# 8ball.net
KiCad netlist of a schematic drawn in EAGLE
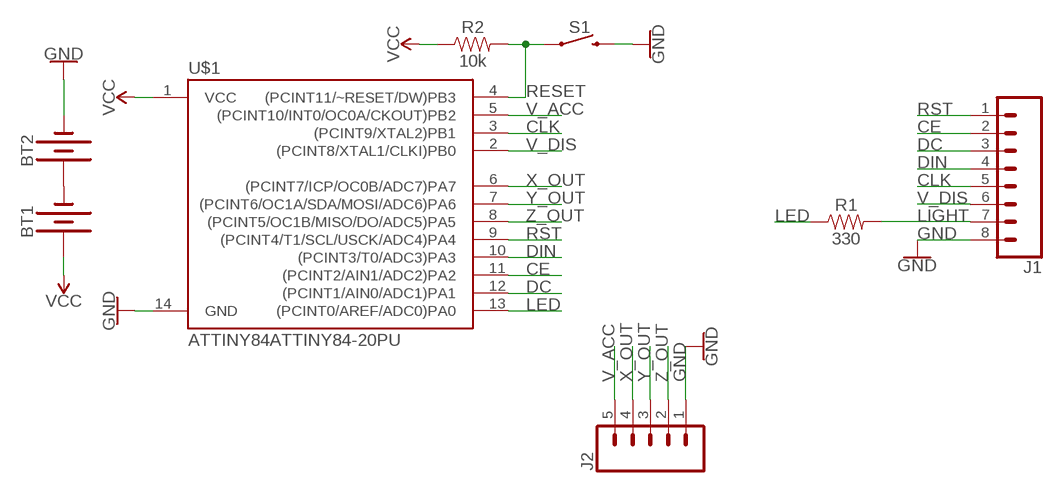
[diagram p0: schematic, sheet 1]

(export (version "E")
  (design (tool "Eeschema 10.0.6"))
  (components
    (comp (ref "BT1")
      (value "BATTERY-AAA")
      (footprint "eagle-import:BATTERY-AAA")
      (libsource (lib "eagle-import") (part "BATTERY-AAA"))
    )
    (comp (ref "BT2")
      (value "BATTERY-AAA")
      (footprint "eagle-import:BATTERY-AAA")
      (libsource (lib "eagle-import") (part "BATTERY-AAA"))
    )
    (comp (ref "J1")
      (value "CONN_08FEMALE_LOCK")
      (footprint "eagle-import:1X08_FEMALE_LOCK")
      (libsource (lib "eagle-import") (part "CONN_08FEMALE_LOCK"))
    )
    (comp (ref "J2")
      (value "CONN_05LOCK")
      (footprint "eagle-import:1X05_LOCK")
      (libsource (lib "eagle-import") (part "CONN_05LOCK"))
    )
    (comp (ref "R1")
      (value "330")
      (footprint "eagle-import:AXIAL-0.3")
      (libsource (lib "eagle-import") (part "330OHM-HORIZ-1/10W-5%"))
    )
    (comp (ref "R2")
      (value "10k")
      (footprint "eagle-import:AXIAL-0.3")
      (libsource (lib "eagle-import") (part "10KOHM-HORIZ-1/6W-5%"))
    )
    (comp (ref "S1")
      (value "MOMENTARY-SWITCH-SPST-PTH-6.0MM-KIT")
      (footprint "eagle-import:TACTILE_SWITCH_PTH_6.0MM_KIT")
      (libsource (lib "eagle-import") (part "MOMENTARY-SWITCH-SPST-PTH-6.0MM-KIT"))
    )
    (comp (ref "U$1")
      (value "ATTINY84ATTINY84-20PU")
      (footprint "eagle-import:DIP14")
      (libsource (lib "eagle-import") (part "ATTINY84ATTINY84-20PU"))
    )
  )
  (nets
    (net (code "1") (name "/CE") (class "Default")
      (node (ref "J1") (pin "2") (pinfunction "2_2") (pintype "passive"))
      (node (ref "U$1") (pin "11") (pinfunction "(PCINT2/AIN1/ADC2)PA2_11") (pintype "bidirectional"))
    )
    (net (code "2") (name "/CLK") (class "Default")
      (node (ref "J1") (pin "5") (pinfunction "5_5") (pintype "passive"))
      (node (ref "U$1") (pin "3") (pinfunction "(PCINT9/XTAL2)PB1_3") (pintype "bidirectional"))
    )
    (net (code "3") (name "/DC") (class "Default")
      (node (ref "J1") (pin "3") (pinfunction "3_3") (pintype "passive"))
      (node (ref "U$1") (pin "12") (pinfunction "(PCINT1/AIN0/ADC1)PA1_12") (pintype "bidirectional"))
    )
    (net (code "4") (name "/DIN") (class "Default")
      (node (ref "J1") (pin "4") (pinfunction "4_4") (pintype "passive"))
      (node (ref "U$1") (pin "10") (pinfunction "(PCINT3/T0/ADC3)PA3_10") (pintype "bidirectional"))
    )
    (net (code "5") (name "/LED") (class "Default")
      (node (ref "R1") (pin "P$1") (pinfunction "1_P$1") (pintype "passive"))
      (node (ref "U$1") (pin "13") (pinfunction "(PCINT0/AREF/ADC0)PA0_13") (pintype "bidirectional"))
    )
    (net (code "6") (name "/LIGHT") (class "Default")
      (node (ref "J1") (pin "7") (pinfunction "7_7") (pintype "passive"))
      (node (ref "R1") (pin "P$2") (pinfunction "2_P$2") (pintype "passive"))
    )
    (net (code "7") (name "/RESET") (class "Default")
      (node (ref "R2") (pin "P$2") (pinfunction "2_P$2") (pintype "passive"))
      (node (ref "S1") (pin "1") (pinfunction "1_1") (pintype "passive"))
      (node (ref "U$1") (pin "4") (pinfunction "(PCINT11/~{RESET/DW})PB3_4") (pintype "bidirectional"))
    )
    (net (code "8") (name "/RST") (class "Default")
      (node (ref "J1") (pin "1") (pinfunction "1_1") (pintype "passive"))
      (node (ref "U$1") (pin "9") (pinfunction "(PCINT4/T1/SCL/USCK/ADC4)PA4_9") (pintype "bidirectional"))
    )
    (net (code "9") (name "/V_ACC") (class "Default")
      (node (ref "J2") (pin "5") (pinfunction "5_5") (pintype "passive"))
      (node (ref "U$1") (pin "5") (pinfunction "(PCINT10/INT0/OC0A/CKOUT)PB2_5") (pintype "bidirectional"))
    )
    (net (code "10") (name "/V_DIS") (class "Default")
      (node (ref "J1") (pin "6") (pinfunction "6_6") (pintype "passive"))
      (node (ref "U$1") (pin "2") (pinfunction "(PCINT8/XTAL1/CLKI)PB0_2") (pintype "bidirectional"))
    )
    (net (code "11") (name "/X_OUT") (class "Default")
      (node (ref "J2") (pin "4") (pinfunction "4_4") (pintype "passive"))
      (node (ref "U$1") (pin "6") (pinfunction "(PCINT7/ICP/OC0B/ADC7)PA7_6") (pintype "bidirectional"))
    )
    (net (code "12") (name "/Y_OUT") (class "Default")
      (node (ref "J2") (pin "3") (pinfunction "3_3") (pintype "passive"))
      (node (ref "U$1") (pin "7") (pinfunction "(PCINT6/OC1A/SDA/MOSI/ADC6)PA6_7") (pintype "bidirectional"))
    )
    (net (code "13") (name "/Z_OUT") (class "Default")
      (node (ref "J2") (pin "2") (pinfunction "2_2") (pintype "passive"))
      (node (ref "U$1") (pin "8") (pinfunction "(PCINT5/OC1B/MISO/DO/ADC5)PA5_8") (pintype "bidirectional"))
    )
    (net (code "14") (name "GND") (class "Default")
      (node (ref "BT2") (pin "GND@1") (pinfunction "-_GND@1") (pintype "power_in"))
      (node (ref "J1") (pin "8") (pinfunction "8_8") (pintype "passive"))
      (node (ref "J2") (pin "1") (pinfunction "1_1") (pintype "passive"))
      (node (ref "S1") (pin "3") (pinfunction "2_3") (pintype "passive"))
      (node (ref "U$1") (pin "14") (pinfunction "GND_14") (pintype "bidirectional"))
    )
    (net (code "15") (name "Net-(BT1--)") (class "Default")
      (node (ref "BT1") (pin "GND@1") (pinfunction "-_GND@1") (pintype "power_in"))
      (node (ref "BT2") (pin "PWR@1") (pinfunction "+_PWR@1") (pintype "power_in"))
    )
    (net (code "16") (name "VCC") (class "Default")
      (node (ref "BT1") (pin "PWR@1") (pinfunction "+_PWR@1") (pintype "power_in"))
      (node (ref "R2") (pin "P$1") (pinfunction "1_P$1") (pintype "passive"))
      (node (ref "U$1") (pin "1") (pinfunction "VCC_1") (pintype "bidirectional"))
    )
  )
)
